# MT-DS_v1_1.net
KiCad netlist of a schematic drawn in EAGLE
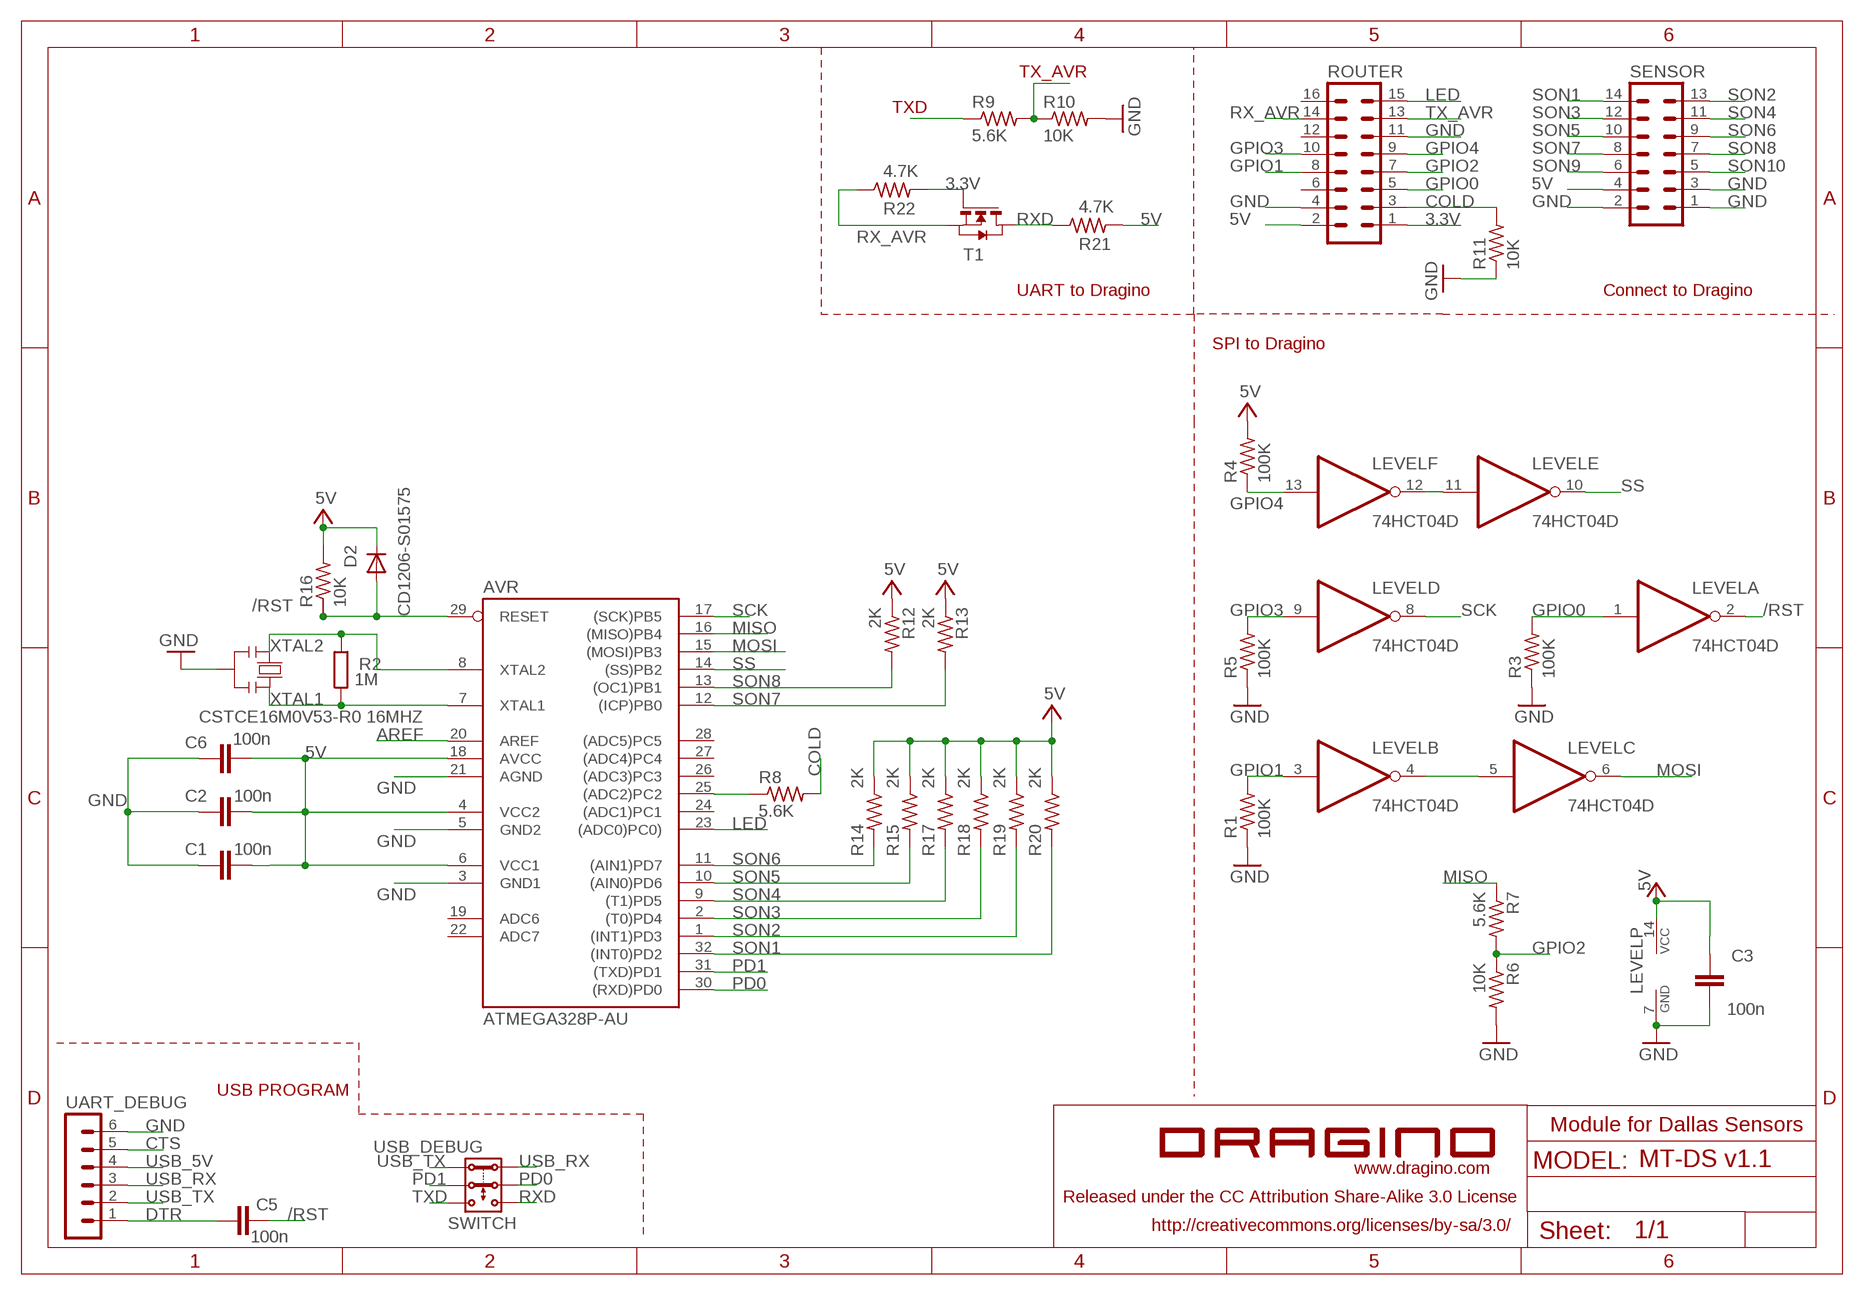
[diagram p0: schematic, sheet 1]

(export (version "E")
  (design (tool "Eeschema 10.0.6"))
  (components
    (comp (ref "AVR")
      (value "ATMEGA328P-AU")
      (footprint "eagle-import:SMARTPRJ_TQFP32-08")
      (libsource (lib "eagle-import") (part "SMARTPRJ_ATMEGA328P-AU"))
    )
    (comp (ref "C1")
      (value "100n")
      (footprint "eagle-import:C0402")
      (libsource (lib "eagle-import") (part "C-EUC0402"))
    )
    (comp (ref "C2")
      (value "100n")
      (footprint "eagle-import:C0402")
      (libsource (lib "eagle-import") (part "C-EUC0402"))
    )
    (comp (ref "C3")
      (value "100n")
      (footprint "eagle-import:C0402")
      (libsource (lib "eagle-import") (part "C-EUC0402"))
    )
    (comp (ref "C5")
      (value "100n")
      (footprint "eagle-import:C0402")
      (libsource (lib "eagle-import") (part "C-EUC0402"))
    )
    (comp (ref "C6")
      (value "100n")
      (footprint "eagle-import:C0402")
      (libsource (lib "eagle-import") (part "C-EUC0402"))
    )
    (comp (ref "D2")
      (value "CD1206-S01575")
      (footprint "eagle-import:MINIMELF")
      (libsource (lib "eagle-import") (part "DIODE-MINIMELF"))
    )
    (comp (ref "LEVEL")
      (value "74HCT04D")
      (footprint "eagle-import:SO14")
      (libsource (lib "eagle-import") (part "7404DHCT"))
    )
    (comp (ref "R1")
      (value "100K")
      (footprint "eagle-import:R0402")
      (libsource (lib "eagle-import") (part "R-US_R0402"))
    )
    (comp (ref "R2")
      (value "1M")
      (footprint "eagle-import:R0402")
      (libsource (lib "eagle-import") (part "R-EU_R0402"))
    )
    (comp (ref "R3")
      (value "100K")
      (footprint "eagle-import:R0402")
      (libsource (lib "eagle-import") (part "R-US_R0402"))
    )
    (comp (ref "R4")
      (value "100K")
      (footprint "eagle-import:R0402")
      (libsource (lib "eagle-import") (part "R-US_R0402"))
    )
    (comp (ref "R5")
      (value "100K")
      (footprint "eagle-import:R0402")
      (libsource (lib "eagle-import") (part "R-US_R0402"))
    )
    (comp (ref "R6")
      (value "10K")
      (footprint "eagle-import:R0402")
      (libsource (lib "eagle-import") (part "R-US_R0402"))
    )
    (comp (ref "R7")
      (value "5.6K")
      (footprint "eagle-import:R0402")
      (libsource (lib "eagle-import") (part "R-US_R0402"))
    )
    (comp (ref "R8")
      (value "5.6K")
      (footprint "eagle-import:R0402")
      (libsource (lib "eagle-import") (part "R-US_R0402"))
    )
    (comp (ref "R9")
      (value "5.6K")
      (footprint "eagle-import:R0402")
      (libsource (lib "eagle-import") (part "R-US_R0402"))
    )
    (comp (ref "R10")
      (value "10K")
      (footprint "eagle-import:R0402")
      (libsource (lib "eagle-import") (part "R-US_R0402"))
    )
    (comp (ref "R11")
      (value "10K")
      (footprint "eagle-import:R0402")
      (libsource (lib "eagle-import") (part "R-US_R0402"))
    )
    (comp (ref "R12")
      (value "2K")
      (footprint "eagle-import:R0805")
      (libsource (lib "eagle-import") (part "R-US_R0805"))
    )
    (comp (ref "R13")
      (value "2K")
      (footprint "eagle-import:R0805")
      (libsource (lib "eagle-import") (part "R-US_R0805"))
    )
    (comp (ref "R14")
      (value "2K")
      (footprint "eagle-import:R0805")
      (libsource (lib "eagle-import") (part "R-US_R0805"))
    )
    (comp (ref "R15")
      (value "2K")
      (footprint "eagle-import:R0805")
      (libsource (lib "eagle-import") (part "R-US_R0805"))
    )
    (comp (ref "R16")
      (value "10K")
      (footprint "eagle-import:R0402")
      (libsource (lib "eagle-import") (part "R-US_R0402"))
    )
    (comp (ref "R17")
      (value "2K")
      (footprint "eagle-import:R0805")
      (libsource (lib "eagle-import") (part "R-US_R0805"))
    )
    (comp (ref "R18")
      (value "2K")
      (footprint "eagle-import:R0805")
      (libsource (lib "eagle-import") (part "R-US_R0805"))
    )
    (comp (ref "R19")
      (value "2K")
      (footprint "eagle-import:R0805")
      (libsource (lib "eagle-import") (part "R-US_R0805"))
    )
    (comp (ref "R20")
      (value "2K")
      (footprint "eagle-import:R0805")
      (libsource (lib "eagle-import") (part "R-US_R0805"))
    )
    (comp (ref "R21")
      (value "4.7K")
      (footprint "eagle-import:R0805")
      (libsource (lib "eagle-import") (part "R-US_R0805"))
    )
    (comp (ref "R22")
      (value "4.7K")
      (footprint "eagle-import:R0805")
      (libsource (lib "eagle-import") (part "R-US_R0805"))
    )
    (comp (ref "ROUTER")
      (value "MA08-2")
      (footprint "eagle-import:MA08-2")
      (libsource (lib "eagle-import") (part "MA08-2"))
    )
    (comp (ref "SENSOR")
      (value "MA07-2")
      (footprint "eagle-import:MA07-2")
      (libsource (lib "eagle-import") (part "MA07-2"))
    )
    (comp (ref "T1")
      (value "NMOSFET-SOT23")
      (footprint "eagle-import:SOT-23")
      (libsource (lib "eagle-import") (part "NMOSFET-SOT23"))
    )
    (comp (ref "U$1")
      (value "LOGO-SILK")
      (footprint "eagle-import:LOGO-SILK-15MM")
      (libsource (lib "eagle-import") (part "LOGO-SILK"))
    )
    (comp (ref "UART_DEBUG")
      (value "MA06-1")
      (footprint "eagle-import:MA06-1")
      (libsource (lib "eagle-import") (part "MA06-1"))
    )
    (comp (ref "USB_DEBUG")
      (value "SWITCH")
      (footprint "eagle-import:2P2T")
      (libsource (lib "eagle-import") (part "SWITCH-2P2T"))
    )
    (comp (ref "Y2")
      (value "CSTCE16M0V53-R0 16MHZ")
      (footprint "eagle-import:RESONATOR")
      (libsource (lib "eagle-import") (part "RESONATORMU"))
    )
  )
  (nets
    (net (code "1") (name "/3.3V") (class "Default")
      (node (ref "R22") (pin "2") (pinfunction "2_2") (pintype "passive"))
      (node (ref "ROUTER") (pin "1") (pinfunction "1_1") (pintype "passive"))
      (node (ref "T1") (pin "3") (pinfunction "G_3") (pintype "passive"))
    )
    (net (code "2") (name "/AREF") (class "Default")
      (node (ref "AVR") (pin "20") (pinfunction "AREF_20") (pintype "passive"))
    )
    (net (code "3") (name "/COLD") (class "Default")
      (node (ref "R11") (pin "2") (pinfunction "2_2") (pintype "passive"))
      (node (ref "R8") (pin "2") (pinfunction "2_2") (pintype "passive"))
      (node (ref "ROUTER") (pin "3") (pinfunction "3_3") (pintype "passive"))
    )
    (net (code "4") (name "/CTS") (class "Default")
      (node (ref "UART_DEBUG") (pin "5") (pinfunction "5_5") (pintype "passive"))
    )
    (net (code "5") (name "/DTR") (class "Default")
      (node (ref "C5") (pin "1") (pinfunction "1_1") (pintype "passive"))
      (node (ref "UART_DEBUG") (pin "1") (pinfunction "1_1") (pintype "passive"))
    )
    (net (code "6") (name "/GPIO0") (class "Default")
      (node (ref "LEVEL") (pin "1") (pinfunction "I_1") (pintype "input"))
      (node (ref "R3") (pin "2") (pinfunction "2_2") (pintype "passive"))
      (node (ref "ROUTER") (pin "5") (pinfunction "5_5") (pintype "passive"))
    )
    (net (code "7") (name "/GPIO1") (class "Default")
      (node (ref "LEVEL") (pin "3") (pinfunction "I_3") (pintype "input"))
      (node (ref "R1") (pin "2") (pinfunction "2_2") (pintype "passive"))
      (node (ref "ROUTER") (pin "8") (pinfunction "8_8") (pintype "passive"))
    )
    (net (code "8") (name "/GPIO2") (class "Default")
      (node (ref "R6") (pin "1") (pinfunction "1_1") (pintype "passive"))
      (node (ref "R7") (pin "2") (pinfunction "2_2") (pintype "passive"))
      (node (ref "ROUTER") (pin "7") (pinfunction "7_7") (pintype "passive"))
    )
    (net (code "9") (name "/GPIO3") (class "Default")
      (node (ref "LEVEL") (pin "9") (pinfunction "I_9") (pintype "input"))
      (node (ref "R5") (pin "2") (pinfunction "2_2") (pintype "passive"))
      (node (ref "ROUTER") (pin "10") (pinfunction "10_10") (pintype "passive"))
    )
    (net (code "10") (name "/GPIO4") (class "Default")
      (node (ref "LEVEL") (pin "13") (pinfunction "I_13") (pintype "input"))
      (node (ref "R4") (pin "1") (pinfunction "1_1") (pintype "passive"))
      (node (ref "ROUTER") (pin "9") (pinfunction "9_9") (pintype "passive"))
    )
    (net (code "11") (name "/LED") (class "Default")
      (node (ref "AVR") (pin "23") (pinfunction "(ADC0)PC0)_23") (pintype "bidirectional"))
      (node (ref "ROUTER") (pin "15") (pinfunction "15_15") (pintype "passive"))
    )
    (net (code "12") (name "/MISO") (class "Default")
      (node (ref "AVR") (pin "16") (pinfunction "(MISO)PB4_16") (pintype "bidirectional"))
      (node (ref "R7") (pin "1") (pinfunction "1_1") (pintype "passive"))
    )
    (net (code "13") (name "/MOSI") (class "Default")
      (node (ref "AVR") (pin "15") (pinfunction "(MOSI)PB3_15") (pintype "bidirectional"))
      (node (ref "LEVEL") (pin "6") (pinfunction "O_6") (pintype "output"))
    )
    (net (code "14") (name "/PD0") (class "Default")
      (node (ref "AVR") (pin "30") (pinfunction "(RXD)PD0_30") (pintype "bidirectional"))
      (node (ref "USB_DEBUG") (pin "2.1") (pinfunction "2.1_2.1") (pintype "passive"))
    )
    (net (code "15") (name "/PD1") (class "Default")
      (node (ref "AVR") (pin "31") (pinfunction "(TXD)PD1_31") (pintype "bidirectional"))
      (node (ref "USB_DEBUG") (pin "2.2") (pinfunction "2.2_2.2") (pintype "passive"))
    )
    (net (code "16") (name "/RXD") (class "Default")
      (node (ref "R21") (pin "1") (pinfunction "1_1") (pintype "passive"))
      (node (ref "T1") (pin "1") (pinfunction "D_1") (pintype "passive"))
      (node (ref "USB_DEBUG") (pin "3.1") (pinfunction "3.1_3.1") (pintype "passive"))
    )
    (net (code "17") (name "/RX_AVR") (class "Default")
      (node (ref "R22") (pin "1") (pinfunction "1_1") (pintype "passive"))
      (node (ref "ROUTER") (pin "14") (pinfunction "14_14") (pintype "passive"))
      (node (ref "T1") (pin "2") (pinfunction "S_2") (pintype "passive"))
    )
    (net (code "18") (name "/SCK") (class "Default")
      (node (ref "AVR") (pin "17") (pinfunction "(SCK)PB5_17") (pintype "bidirectional"))
      (node (ref "LEVEL") (pin "8") (pinfunction "O_8") (pintype "output"))
    )
    (net (code "19") (name "/SON1") (class "Default")
      (node (ref "AVR") (pin "32") (pinfunction "(INT0)PD2_32") (pintype "bidirectional"))
      (node (ref "R20") (pin "2") (pinfunction "2_2") (pintype "passive"))
      (node (ref "SENSOR") (pin "14") (pinfunction "14_14") (pintype "passive"))
    )
    (net (code "20") (name "/SON2") (class "Default")
      (node (ref "AVR") (pin "1") (pinfunction "(INT1)PD3_1") (pintype "bidirectional"))
      (node (ref "R19") (pin "2") (pinfunction "2_2") (pintype "passive"))
      (node (ref "SENSOR") (pin "13") (pinfunction "13_13") (pintype "passive"))
    )
    (net (code "21") (name "/SON3") (class "Default")
      (node (ref "AVR") (pin "2") (pinfunction "(T0)PD4_2") (pintype "bidirectional"))
      (node (ref "R18") (pin "2") (pinfunction "2_2") (pintype "passive"))
      (node (ref "SENSOR") (pin "12") (pinfunction "12_12") (pintype "passive"))
    )
    (net (code "22") (name "/SON4") (class "Default")
      (node (ref "AVR") (pin "9") (pinfunction "(T1)PD5_9") (pintype "bidirectional"))
      (node (ref "R17") (pin "2") (pinfunction "2_2") (pintype "passive"))
      (node (ref "SENSOR") (pin "11") (pinfunction "11_11") (pintype "passive"))
    )
    (net (code "23") (name "/SON5") (class "Default")
      (node (ref "AVR") (pin "10") (pinfunction "(AIN0)PD6_10") (pintype "bidirectional"))
      (node (ref "R15") (pin "2") (pinfunction "2_2") (pintype "passive"))
      (node (ref "SENSOR") (pin "10") (pinfunction "10_10") (pintype "passive"))
    )
    (net (code "24") (name "/SON6") (class "Default")
      (node (ref "AVR") (pin "11") (pinfunction "(AIN1)PD7_11") (pintype "bidirectional"))
      (node (ref "R14") (pin "2") (pinfunction "2_2") (pintype "passive"))
      (node (ref "SENSOR") (pin "9") (pinfunction "9_9") (pintype "passive"))
    )
    (net (code "25") (name "/SON7") (class "Default")
      (node (ref "AVR") (pin "12") (pinfunction "(ICP)PB0_12") (pintype "bidirectional"))
      (node (ref "R13") (pin "2") (pinfunction "2_2") (pintype "passive"))
      (node (ref "SENSOR") (pin "8") (pinfunction "8_8") (pintype "passive"))
    )
    (net (code "26") (name "/SON8") (class "Default")
      (node (ref "AVR") (pin "13") (pinfunction "(OC1)PB1_13") (pintype "bidirectional"))
      (node (ref "R12") (pin "2") (pinfunction "2_2") (pintype "passive"))
      (node (ref "SENSOR") (pin "7") (pinfunction "7_7") (pintype "passive"))
    )
    (net (code "27") (name "/SON9") (class "Default")
      (node (ref "SENSOR") (pin "6") (pinfunction "6_6") (pintype "passive"))
    )
    (net (code "28") (name "/SON10") (class "Default")
      (node (ref "SENSOR") (pin "5") (pinfunction "5_5") (pintype "passive"))
    )
    (net (code "29") (name "/SS") (class "Default")
      (node (ref "AVR") (pin "14") (pinfunction "(SS)PB2_14") (pintype "bidirectional"))
      (node (ref "LEVEL") (pin "10") (pinfunction "O_10") (pintype "output"))
    )
    (net (code "30") (name "/TXD") (class "Default")
      (node (ref "R9") (pin "1") (pinfunction "1_1") (pintype "passive"))
      (node (ref "USB_DEBUG") (pin "3.2") (pinfunction "3.2_3.2") (pintype "passive"))
    )
    (net (code "31") (name "/TX_AVR") (class "Default")
      (node (ref "R10") (pin "1") (pinfunction "1_1") (pintype "passive"))
      (node (ref "R9") (pin "2") (pinfunction "2_2") (pintype "passive"))
      (node (ref "ROUTER") (pin "13") (pinfunction "13_13") (pintype "passive"))
    )
    (net (code "32") (name "/USB_5V") (class "Default")
      (node (ref "UART_DEBUG") (pin "4") (pinfunction "4_4") (pintype "passive"))
    )
    (net (code "33") (name "/USB_RX") (class "Default")
      (node (ref "UART_DEBUG") (pin "3") (pinfunction "3_3") (pintype "passive"))
      (node (ref "USB_DEBUG") (pin "1.1") (pinfunction "1.1_1.1") (pintype "passive"))
    )
    (net (code "34") (name "/USB_TX") (class "Default")
      (node (ref "UART_DEBUG") (pin "2") (pinfunction "2_2") (pintype "passive"))
      (node (ref "USB_DEBUG") (pin "1.2") (pinfunction "1.2_1.2") (pintype "passive"))
    )
    (net (code "35") (name "/XTAL1") (class "Default")
      (node (ref "AVR") (pin "7") (pinfunction "XTAL1_7") (pintype "bidirectional"))
      (node (ref "R2") (pin "1") (pinfunction "1_1") (pintype "passive"))
      (node (ref "Y2") (pin "3") (pinfunction "3_3") (pintype "passive"))
    )
    (net (code "36") (name "/XTAL2") (class "Default")
      (node (ref "AVR") (pin "8") (pinfunction "XTAL2_8") (pintype "bidirectional"))
      (node (ref "R2") (pin "2") (pinfunction "2_2") (pintype "passive"))
      (node (ref "Y2") (pin "1") (pinfunction "1_1") (pintype "passive"))
    )
    (net (code "37") (name "/{slash}RST") (class "Default")
      (node (ref "AVR") (pin "29") (pinfunction "RESET_29") (pintype "input"))
      (node (ref "C5") (pin "2") (pinfunction "2_2") (pintype "passive"))
      (node (ref "D2") (pin "A") (pinfunction "A_A") (pintype "passive"))
      (node (ref "LEVEL") (pin "2") (pinfunction "O_2") (pintype "output"))
      (node (ref "R16") (pin "1") (pinfunction "1_1") (pintype "passive"))
    )
    (net (code "38") (name "5V") (class "Default")
      (node (ref "AVR") (pin "18") (pinfunction "AVCC_18") (pintype "power_in"))
      (node (ref "AVR") (pin "4") (pinfunction "VCC2_4") (pintype "power_in"))
      (node (ref "AVR") (pin "6") (pinfunction "VCC1_6") (pintype "power_in"))
      (node (ref "C1") (pin "1") (pinfunction "1_1") (pintype "passive"))
      (node (ref "C2") (pin "1") (pinfunction "1_1") (pintype "passive"))
      (node (ref "C3") (pin "2") (pinfunction "2_2") (pintype "passive"))
      (node (ref "C6") (pin "1") (pinfunction "1_1") (pintype "passive"))
      (node (ref "D2") (pin "C") (pinfunction "C_C") (pintype "passive"))
      (node (ref "LEVEL") (pin "14") (pinfunction "VCC_14") (pintype "power_in"))
      (node (ref "R12") (pin "1") (pinfunction "1_1") (pintype "passive"))
      (node (ref "R13") (pin "1") (pinfunction "1_1") (pintype "passive"))
      (node (ref "R14") (pin "1") (pinfunction "1_1") (pintype "passive"))
      (node (ref "R15") (pin "1") (pinfunction "1_1") (pintype "passive"))
      (node (ref "R16") (pin "2") (pinfunction "2_2") (pintype "passive"))
      (node (ref "R17") (pin "1") (pinfunction "1_1") (pintype "passive"))
      (node (ref "R18") (pin "1") (pinfunction "1_1") (pintype "passive"))
      (node (ref "R19") (pin "1") (pinfunction "1_1") (pintype "passive"))
      (node (ref "R20") (pin "1") (pinfunction "1_1") (pintype "passive"))
      (node (ref "R21") (pin "2") (pinfunction "2_2") (pintype "passive"))
      (node (ref "R4") (pin "2") (pinfunction "2_2") (pintype "passive"))
      (node (ref "ROUTER") (pin "2") (pinfunction "2_2") (pintype "passive"))
      (node (ref "SENSOR") (pin "4") (pinfunction "4_4") (pintype "passive"))
    )
    (net (code "39") (name "GND") (class "Default")
      (node (ref "AVR") (pin "21") (pinfunction "AGND_21") (pintype "power_in"))
      (node (ref "AVR") (pin "3") (pinfunction "GND1_3") (pintype "power_in"))
      (node (ref "AVR") (pin "5") (pinfunction "GND2_5") (pintype "power_in"))
      (node (ref "C1") (pin "2") (pinfunction "2_2") (pintype "passive"))
      (node (ref "C2") (pin "2") (pinfunction "2_2") (pintype "passive"))
      (node (ref "C3") (pin "1") (pinfunction "1_1") (pintype "passive"))
      (node (ref "C6") (pin "2") (pinfunction "2_2") (pintype "passive"))
      (node (ref "LEVEL") (pin "7") (pinfunction "GND_7") (pintype "power_in"))
      (node (ref "R1") (pin "1") (pinfunction "1_1") (pintype "passive"))
      (node (ref "R10") (pin "2") (pinfunction "2_2") (pintype "passive"))
      (node (ref "R11") (pin "1") (pinfunction "1_1") (pintype "passive"))
      (node (ref "R3") (pin "1") (pinfunction "1_1") (pintype "passive"))
      (node (ref "R5") (pin "1") (pinfunction "1_1") (pintype "passive"))
      (node (ref "R6") (pin "2") (pinfunction "2_2") (pintype "passive"))
      (node (ref "ROUTER") (pin "11") (pinfunction "11_11") (pintype "passive"))
      (node (ref "ROUTER") (pin "4") (pinfunction "4_4") (pintype "passive"))
      (node (ref "SENSOR") (pin "1") (pinfunction "1_1") (pintype "passive"))
      (node (ref "SENSOR") (pin "2") (pinfunction "2_2") (pintype "passive"))
      (node (ref "SENSOR") (pin "3") (pinfunction "3_3") (pintype "passive"))
      (node (ref "UART_DEBUG") (pin "6") (pinfunction "6_6") (pintype "passive"))
      (node (ref "Y2") (pin "2") (pinfunction "2_2") (pintype "passive"))
    )
    (net (code "40") (name "Net-(AVR-(ADC2)PC2)") (class "Default")
      (node (ref "AVR") (pin "25") (pinfunction "(ADC2)PC2_25") (pintype "bidirectional"))
      (node (ref "R8") (pin "1") (pinfunction "1_1") (pintype "passive"))
    )
    (net (code "41") (name "Net-(LEVELB-O)") (class "Default")
      (node (ref "LEVEL") (pin "4") (pinfunction "O_4") (pintype "output"))
      (node (ref "LEVEL") (pin "5") (pinfunction "I_5") (pintype "input"))
    )
    (net (code "42") (name "Net-(LEVELE-I)") (class "Default")
      (node (ref "LEVEL") (pin "11") (pinfunction "I_11") (pintype "input"))
      (node (ref "LEVEL") (pin "12") (pinfunction "O_12") (pintype "output"))
    )
    (net (code "43") (name "unconnected-(AVR-(ADC1)PC1-Pad24)") (class "Default")
      (node (ref "AVR") (pin "24") (pinfunction "(ADC1)PC1_24") (pintype "bidirectional"))
    )
    (net (code "44") (name "unconnected-(AVR-(ADC3)PC3-Pad26)") (class "Default")
      (node (ref "AVR") (pin "26") (pinfunction "(ADC3)PC3_26") (pintype "bidirectional"))
    )
    (net (code "45") (name "unconnected-(AVR-(ADC4)PC4-Pad27)") (class "Default")
      (node (ref "AVR") (pin "27") (pinfunction "(ADC4)PC4_27") (pintype "bidirectional"))
    )
    (net (code "46") (name "unconnected-(AVR-(ADC5)PC5-Pad28)") (class "Default")
      (node (ref "AVR") (pin "28") (pinfunction "(ADC5)PC5_28") (pintype "bidirectional"))
    )
    (net (code "47") (name "unconnected-(AVR-ADC6-Pad19)") (class "Default")
      (node (ref "AVR") (pin "19") (pinfunction "ADC6_19") (pintype "bidirectional"))
    )
    (net (code "48") (name "unconnected-(AVR-ADC7-Pad22)") (class "Default")
      (node (ref "AVR") (pin "22") (pinfunction "ADC7_22") (pintype "bidirectional"))
    )
    (net (code "49") (name "unconnected-(ROUTER-Pad6)") (class "Default")
      (node (ref "ROUTER") (pin "6") (pinfunction "6_6") (pintype "passive"))
    )
    (net (code "50") (name "unconnected-(ROUTER-Pad12)") (class "Default")
      (node (ref "ROUTER") (pin "12") (pinfunction "12_12") (pintype "passive"))
    )
    (net (code "51") (name "unconnected-(ROUTER-Pad16)") (class "Default")
      (node (ref "ROUTER") (pin "16") (pinfunction "16_16") (pintype "passive"))
    )
  )
)
